# ArmDebuger_5-7_DAPLink_V2.net
KiCad netlist of a schematic drawn in Altium Designer
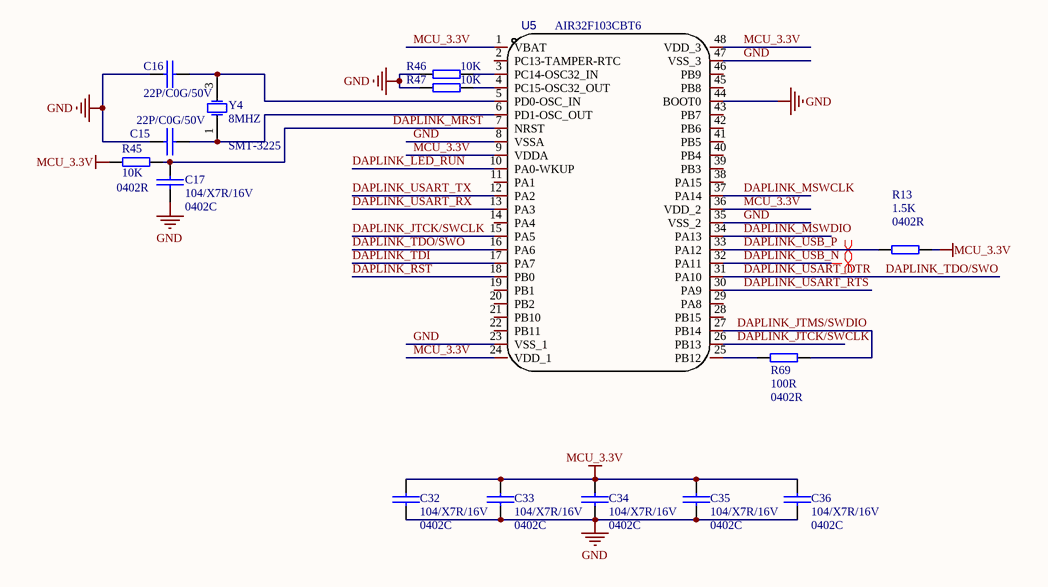
[diagram p0: ArmDebuger(5-7)DAPLink_V2.SchDoc]

(export (version "E")
  (design (tool "Eeschema 10.0.6"))
  (components
    (comp (ref "C15") (value "22P/C0G/50V") (footprint "0402C-SMD-M") (libsource (lib "*") (part "CAP")))
    (comp (ref "C16") (value "22P/C0G/50V") (footprint "0402C-SMD-M") (libsource (lib "*") (part "CAP")))
    (comp (ref "C17")
      (value "104/X7R/16V")
      (footprint "0402C-SMD-M")
      (fields (field (name "FP") "0402C"))
      (libsource (lib "*") (part "CAP"))
    )
    (comp (ref "C32")
      (value "104/X7R/16V")
      (footprint "0402C-SMD-M")
      (fields (field (name "FP") "0402C"))
      (libsource (lib "*") (part "CAP"))
    )
    (comp (ref "C33")
      (value "104/X7R/16V")
      (footprint "0402C-SMD-M")
      (fields (field (name "FP") "0402C"))
      (libsource (lib "*") (part "CAP"))
    )
    (comp (ref "C34")
      (value "104/X7R/16V")
      (footprint "0402C-SMD-M")
      (fields (field (name "FP") "0402C"))
      (libsource (lib "*") (part "CAP"))
    )
    (comp (ref "C35")
      (value "104/X7R/16V")
      (footprint "0402C-SMD-M")
      (fields (field (name "FP") "0402C"))
      (libsource (lib "*") (part "CAP"))
    )
    (comp (ref "C36")
      (value "104/X7R/16V")
      (footprint "0402C-SMD-M")
      (fields (field (name "FP") "0402C"))
      (libsource (lib "*") (part "CAP"))
    )
    (comp (ref "R13")
      (value "1.5K")
      (footprint "0402R-SMD-M")
      (fields (field (name "FP") "0402R"))
      (libsource (lib "*") (part "RES"))
    )
    (comp (ref "R45")
      (value "10K")
      (footprint "0402R-SMD-M")
      (fields (field (name "FP") "0402R"))
      (libsource (lib "*") (part "RES"))
    )
    (comp (ref "R46") (value "10K") (footprint "0402R-SMD-M") (libsource (lib "*") (part "RES")))
    (comp (ref "R47") (value "10K") (footprint "0402R-SMD-M") (libsource (lib "*") (part "RES")))
    (comp (ref "R69")
      (value "100R")
      (footprint "0402R-SMD-M")
      (fields (field (name "FP") "0402R"))
      (libsource (lib "*") (part "RES"))
    )
    (comp (ref "U5")
      (value "AIR32F103CBT6")
      (footprint "LQFP48_L")
      (libsource (lib "altium-import") (part "root_0_STM32F103C8T6TR_"))
    )
    (comp (ref "Y4")
      (value "8MHZ")
      (footprint "CRYSTAL-SMT-3225")
      (description "贴片晶振")
      (fields (field (name "FP") "SMT-3225"))
      (libsource (lib "CrystalOscillator") (part "SMD-3225_4P  25MHZ 12PF 10PPM"))
    )
  )
  (nets
    (net (code "1") (name "/DAPLINK_JTCK{slash}SWCLK") (class "Default")
      (node (ref "U5") (pin "15") (pinfunction "PA5_15") (pintype "passive"))
      (node (ref "U5") (pin "26") (pinfunction "PB13_26") (pintype "passive"))
    )
    (net (code "2") (name "/DAPLINK_JTMS{slash}SWDIO") (class "Default")
      (node (ref "R69") (pin "2") (pinfunction "2_2") (pintype "passive"))
      (node (ref "U5") (pin "27") (pinfunction "PB14_27") (pintype "passive"))
    )
    (net (code "3") (name "/DAPLINK_LED_RUN") (class "Default")
      (node (ref "U5") (pin "10") (pinfunction "PA0-WKUP_10") (pintype "passive"))
    )
    (net (code "4") (name "/DAPLINK_MRST") (class "Default")
      (node (ref "C17") (pin "2") (pinfunction "1_2") (pintype "passive"))
      (node (ref "R45") (pin "2") (pinfunction "2_2") (pintype "passive"))
      (node (ref "U5") (pin "7") (pinfunction "NRST_7") (pintype "passive"))
    )
    (net (code "5") (name "/DAPLINK_MSWCLK") (class "Default")
      (node (ref "U5") (pin "37") (pinfunction "PA14_37") (pintype "passive"))
    )
    (net (code "6") (name "/DAPLINK_MSWDIO") (class "Default")
      (node (ref "U5") (pin "34") (pinfunction "PA13_34") (pintype "passive"))
    )
    (net (code "7") (name "/DAPLINK_RST") (class "Default")
      (node (ref "U5") (pin "18") (pinfunction "PB0_18") (pintype "passive"))
    )
    (net (code "8") (name "/DAPLINK_TDI") (class "Default")
      (node (ref "U5") (pin "17") (pinfunction "PA7_17") (pintype "passive"))
    )
    (net (code "9") (name "/DAPLINK_TDO{slash}SWO") (class "Default")
      (node (ref "U5") (pin "16") (pinfunction "PA6_16") (pintype "passive"))
      (node (ref "U5") (pin "31") (pinfunction "PA10_31") (pintype "passive"))
    )
    (net (code "10") (name "/DAPLINK_USART_RTS") (class "Default")
      (node (ref "U5") (pin "30") (pinfunction "PA9_30") (pintype "passive"))
    )
    (net (code "11") (name "/DAPLINK_USART_RX") (class "Default")
      (node (ref "U5") (pin "13") (pinfunction "PA3_13") (pintype "passive"))
    )
    (net (code "12") (name "/DAPLINK_USART_TX") (class "Default")
      (node (ref "U5") (pin "12") (pinfunction "PA2_12") (pintype "passive"))
    )
    (net (code "13") (name "/DAPLINK_USB_N") (class "Default")
      (node (ref "U5") (pin "32") (pinfunction "PA11_32") (pintype "passive"))
    )
    (net (code "14") (name "/DAPLINK_USB_P") (class "Default")
      (node (ref "R13") (pin "2") (pinfunction "2_2") (pintype "passive"))
      (node (ref "U5") (pin "33") (pinfunction "PA12_33") (pintype "passive"))
    )
    (net (code "15") (name "GND") (class "Default")
      (node (ref "C15") (pin "1") (pinfunction "1_1") (pintype "passive"))
      (node (ref "C16") (pin "1") (pinfunction "1_1") (pintype "passive"))
      (node (ref "C17") (pin "1") (pinfunction "1_1") (pintype "passive"))
      (node (ref "C32") (pin "1") (pinfunction "1_1") (pintype "passive"))
      (node (ref "C33") (pin "1") (pinfunction "1_1") (pintype "passive"))
      (node (ref "C34") (pin "1") (pinfunction "1_1") (pintype "passive"))
      (node (ref "C35") (pin "1") (pinfunction "1_1") (pintype "passive"))
      (node (ref "C36") (pin "1") (pinfunction "1_1") (pintype "passive"))
      (node (ref "R46") (pin "1") (pinfunction "1_1") (pintype "passive"))
      (node (ref "R47") (pin "1") (pinfunction "1_1") (pintype "passive"))
      (node (ref "U5") (pin "23") (pinfunction "VSS_1_23") (pintype "passive"))
      (node (ref "U5") (pin "35") (pinfunction "VSS_2_35") (pintype "passive"))
      (node (ref "U5") (pin "44") (pinfunction "BOOT0_44") (pintype "passive"))
      (node (ref "U5") (pin "47") (pinfunction "VSS_3_47") (pintype "passive"))
      (node (ref "U5") (pin "8") (pinfunction "VSSA_8") (pintype "passive"))
    )
    (net (code "16") (name "MCU_3.3V") (class "Default")
      (node (ref "C32") (pin "2") (pinfunction "1_2") (pintype "passive"))
      (node (ref "C33") (pin "2") (pinfunction "1_2") (pintype "passive"))
      (node (ref "C34") (pin "2") (pinfunction "1_2") (pintype "passive"))
      (node (ref "C35") (pin "2") (pinfunction "1_2") (pintype "passive"))
      (node (ref "C36") (pin "2") (pinfunction "1_2") (pintype "passive"))
      (node (ref "R13") (pin "1") (pinfunction "1_1") (pintype "passive"))
      (node (ref "R45") (pin "1") (pinfunction "1_1") (pintype "passive"))
      (node (ref "U5") (pin "1") (pinfunction "VBAT_1") (pintype "passive"))
      (node (ref "U5") (pin "24") (pinfunction "VDD_1_24") (pintype "passive"))
      (node (ref "U5") (pin "36") (pinfunction "VDD_2_36") (pintype "passive"))
      (node (ref "U5") (pin "48") (pinfunction "VDD_3_48") (pintype "passive"))
      (node (ref "U5") (pin "9") (pinfunction "VDDA_9") (pintype "passive"))
    )
    (net (code "17") (name "Net-(U5-PB12)") (class "Default")
      (node (ref "R69") (pin "1") (pinfunction "1_1") (pintype "passive"))
      (node (ref "U5") (pin "25") (pinfunction "PB12_25") (pintype "passive"))
    )
    (net (code "18") (name "Net-(U5-PC14-OSC32_IN)") (class "Default")
      (node (ref "R46") (pin "2") (pinfunction "2_2") (pintype "passive"))
      (node (ref "U5") (pin "3") (pinfunction "PC14-OSC32_IN_3") (pintype "passive"))
    )
    (net (code "19") (name "Net-(U5-PC15-OSC32_OUT)") (class "Default")
      (node (ref "R47") (pin "2") (pinfunction "2_2") (pintype "passive"))
      (node (ref "U5") (pin "4") (pinfunction "PC15-OSC32_OUT_4") (pintype "passive"))
    )
    (net (code "20") (name "Net-(U5-PD0-OSC_IN)") (class "Default")
      (node (ref "C16") (pin "2") (pinfunction "1_2") (pintype "passive"))
      (node (ref "U5") (pin "5") (pinfunction "PD0-OSC_IN_5") (pintype "passive"))
      (node (ref "Y4") (pin "3") (pinfunction "OSC2_3") (pintype "passive"))
    )
    (net (code "21") (name "Net-(U5-PD1-OSC_OUT)") (class "Default")
      (node (ref "C15") (pin "2") (pinfunction "1_2") (pintype "passive"))
      (node (ref "U5") (pin "6") (pinfunction "PD1-OSC_OUT_6") (pintype "passive"))
      (node (ref "Y4") (pin "1") (pinfunction "OSC1_1") (pintype "passive"))
    )
    (net (code "22") (name "unconnected-(U5-PA1-Pad11)") (class "Default")
      (node (ref "U5") (pin "11") (pinfunction "PA1_11") (pintype "passive"))
    )
    (net (code "23") (name "unconnected-(U5-PA4-Pad14)") (class "Default")
      (node (ref "U5") (pin "14") (pinfunction "PA4_14") (pintype "passive"))
    )
    (net (code "24") (name "unconnected-(U5-PA8-Pad29)") (class "Default")
      (node (ref "U5") (pin "29") (pinfunction "PA8_29") (pintype "passive"))
    )
    (net (code "25") (name "unconnected-(U5-PA15-Pad38)") (class "Default")
      (node (ref "U5") (pin "38") (pinfunction "PA15_38") (pintype "passive"))
    )
    (net (code "26") (name "unconnected-(U5-PB1-Pad19)") (class "Default")
      (node (ref "U5") (pin "19") (pinfunction "PB1_19") (pintype "passive"))
    )
    (net (code "27") (name "unconnected-(U5-PB2-Pad20)") (class "Default")
      (node (ref "U5") (pin "20") (pinfunction "PB2_20") (pintype "passive"))
    )
    (net (code "28") (name "unconnected-(U5-PB3-Pad39)") (class "Default")
      (node (ref "U5") (pin "39") (pinfunction "PB3_39") (pintype "passive"))
    )
    (net (code "29") (name "unconnected-(U5-PB4-Pad40)") (class "Default")
      (node (ref "U5") (pin "40") (pinfunction "PB4_40") (pintype "passive"))
    )
    (net (code "30") (name "unconnected-(U5-PB5-Pad41)") (class "Default")
      (node (ref "U5") (pin "41") (pinfunction "PB5_41") (pintype "passive"))
    )
    (net (code "31") (name "unconnected-(U5-PB6-Pad42)") (class "Default")
      (node (ref "U5") (pin "42") (pinfunction "PB6_42") (pintype "passive"))
    )
    (net (code "32") (name "unconnected-(U5-PB7-Pad43)") (class "Default")
      (node (ref "U5") (pin "43") (pinfunction "PB7_43") (pintype "passive"))
    )
    (net (code "33") (name "unconnected-(U5-PB8-Pad45)") (class "Default")
      (node (ref "U5") (pin "45") (pinfunction "PB8_45") (pintype "passive"))
    )
    (net (code "34") (name "unconnected-(U5-PB9-Pad46)") (class "Default")
      (node (ref "U5") (pin "46") (pinfunction "PB9_46") (pintype "passive"))
    )
    (net (code "35") (name "unconnected-(U5-PB10-Pad21)") (class "Default")
      (node (ref "U5") (pin "21") (pinfunction "PB10_21") (pintype "passive"))
    )
    (net (code "36") (name "unconnected-(U5-PB11-Pad22)") (class "Default")
      (node (ref "U5") (pin "22") (pinfunction "PB11_22") (pintype "passive"))
    )
    (net (code "37") (name "unconnected-(U5-PB15-Pad28)") (class "Default")
      (node (ref "U5") (pin "28") (pinfunction "PB15_28") (pintype "passive"))
    )
    (net (code "38") (name "unconnected-(U5-PC13-TAMPER-RTC-Pad2)") (class "Default")
      (node (ref "U5") (pin "2") (pinfunction "PC13-TAMPER-RTC_2") (pintype "passive"))
    )
  )
)
